# VCO.net
KiCad netlist of a schematic drawn in Altium Designer
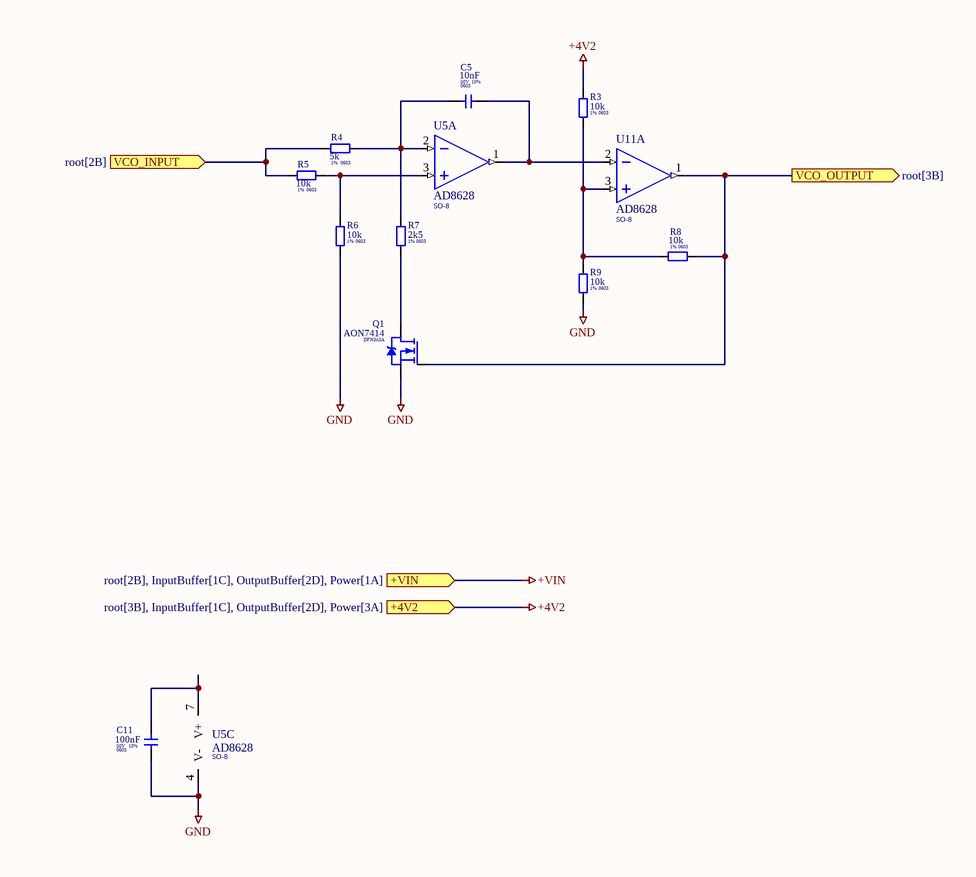
[diagram p0: VCO.SchDoc]

(export (version "E")
  (design (tool "Eeschema 10.0.6"))
  (components
    (comp (ref "C5")
      (value "10nF")
      (footprint "CAPC1608X06M")
      (fields
        (field (name "VOLTAGE") "50V")
        (field (name "TOLERANT") "10%")
        (field (name "PACKAGE") "0603")
        (field (name "Comment") "10nF/50V")
      )
      (libsource (lib "Falcon-SchMain-Lib") (part "C"))
    )
    (comp (ref "C11")
      (value "100nF")
      (footprint "CAPC1608X06M")
      (fields
        (field (name "VOLTAGE") "50V")
        (field (name "TOLERANT") "10%")
        (field (name "PACKAGE") "0603")
        (field (name "Comment") "100nF/50V")
      )
      (libsource (lib "Falcon-SchMain-Lib") (part "C"))
    )
    (comp (ref "Q1")
      (value "AON7414")
      (footprint "SON65P300X90-3L")
      (description "30V, 15A N-Channel MOSFET")
      (fields (field (name "PACKAGE") "DFN3x3A"))
      (libsource (lib "Falcon-SchTransistor-Lib") (part "AON7414"))
    )
    (comp (ref "R3")
      (value "10k")
      (footprint "RESC1608X06L")
      (fields
        (field (name "PACKAGE") "0603")
        (field (name "TOLERANCE") "1%")
        (field (name "Comment") "10k 1%")
      )
      (libsource (lib "") (part "R_1"))
    )
    (comp (ref "R4")
      (value "5k")
      (footprint "RESC1608X06L")
      (fields
        (field (name "PACKAGE") "0603")
        (field (name "TOLERANCE") "1%")
        (field (name "Comment") "5k 1%")
      )
      (libsource (lib "") (part "R_2"))
    )
    (comp (ref "R5")
      (value "10k")
      (footprint "RESC1608X06L")
      (fields
        (field (name "PACKAGE") "0603")
        (field (name "TOLERANCE") "1%")
        (field (name "Comment") "10k 1%")
      )
      (libsource (lib "") (part "R_2"))
    )
    (comp (ref "R6")
      (value "10k")
      (footprint "RESC1608X06L")
      (fields
        (field (name "PACKAGE") "0603")
        (field (name "TOLERANCE") "1%")
        (field (name "Comment") "10k 1%")
      )
      (libsource (lib "") (part "R_1"))
    )
    (comp (ref "R7")
      (value "2k5")
      (footprint "RESC1608X06L")
      (fields
        (field (name "PACKAGE") "0603")
        (field (name "TOLERANCE") "1%")
        (field (name "Comment") "2k5 1%")
      )
      (libsource (lib "") (part "R_1"))
    )
    (comp (ref "R8")
      (value "10k")
      (footprint "RESC1608X06L")
      (fields
        (field (name "PACKAGE") "0603")
        (field (name "TOLERANCE") "1%")
        (field (name "Comment") "10k 1%")
      )
      (libsource (lib "Falcon-SchMain-Lib") (part "R"))
    )
    (comp (ref "R9")
      (value "10k")
      (footprint "RESC1608X06L")
      (fields
        (field (name "PACKAGE") "0603")
        (field (name "TOLERANCE") "1%")
        (field (name "Comment") "10k 1%")
      )
      (libsource (lib "") (part "R_1"))
    )
    (comp (ref "U5")
      (value "AD8628")
      (footprint "SOIC127P600X170-8N")
      (description "Zero-Drift, Single-Supply, Rail-to-Rail Input/Output Operational Amplifier")
      (fields (field (name "PACKAGE") "SO-8"))
      (libsource (lib "") (part "AD8628ARZ_1"))
    )
    (comp (ref "U11")
      (value "AD8628")
      (footprint "SOIC127P600X170-8N")
      (description "Zero-Drift, Single-Supply, Rail-to-Rail Input/Output Operational Amplifier")
      (fields (field (name "PACKAGE") "SO-8"))
      (libsource (lib "") (part "AD8628ARZ_1"))
    )
  )
  (nets
    (net (code "1") (name "+4V2") (class "Default")
      (node (ref "R3") (pin "2") (pinfunction "2_2") (pintype "passive"))
    )
    (net (code "3") (name "/VCO_INPUT") (class "Default")
      (node (ref "R4") (pin "1") (pinfunction "1_1") (pintype "passive"))
      (node (ref "R5") (pin "1") (pinfunction "1_1") (pintype "passive"))
    )
    (net (code "4") (name "/VCO_OUTPUT") (class "Default")
      (node (ref "Q1") (pin "2") (pinfunction "G_2") (pintype "passive"))
      (node (ref "R8") (pin "1") (pinfunction "1_1") (pintype "passive"))
      (node (ref "U11") (pin "1") (pinfunction "OUT_1") (pintype "output"))
    )
    (net (code "5") (name "GND") (class "Default")
      (node (ref "C11") (pin "1") (pinfunction "1_1") (pintype "passive"))
      (node (ref "Q1") (pin "1") (pinfunction "S_1") (pintype "passive"))
      (node (ref "R6") (pin "1") (pinfunction "1_1") (pintype "passive"))
      (node (ref "R9") (pin "1") (pinfunction "1_1") (pintype "passive"))
      (node (ref "U5") (pin "4") (pinfunction "V-_4") (pintype "power_in"))
    )
    (net (code "6") (name "Net-(Q1-D)") (class "Default")
      (node (ref "Q1") (pin "3") (pinfunction "D_3") (pintype "passive"))
      (node (ref "R7") (pin "1") (pinfunction "1_1") (pintype "passive"))
    )
    (net (code "7") (name "Net-(U5A-IN+)") (class "Default")
      (node (ref "R5") (pin "2") (pinfunction "2_2") (pintype "passive"))
      (node (ref "R6") (pin "2") (pinfunction "2_2") (pintype "passive"))
      (node (ref "U5") (pin "3") (pinfunction "IN+_3") (pintype "input"))
    )
    (net (code "8") (name "Net-(U5A-IN-)") (class "Default")
      (node (ref "C5") (pin "1") (pinfunction "1_1") (pintype "passive"))
      (node (ref "R4") (pin "2") (pinfunction "2_2") (pintype "passive"))
      (node (ref "R7") (pin "2") (pinfunction "2_2") (pintype "passive"))
      (node (ref "U5") (pin "2") (pinfunction "IN-_2") (pintype "input"))
    )
    (net (code "9") (name "Net-(U5C-V+)") (class "Default")
      (node (ref "C11") (pin "2") (pinfunction "2_2") (pintype "passive"))
      (node (ref "U5") (pin "7") (pinfunction "V+_7") (pintype "power_in"))
    )
    (net (code "10") (name "Net-(U11A-IN+)") (class "Default")
      (node (ref "R3") (pin "1") (pinfunction "1_1") (pintype "passive"))
      (node (ref "R8") (pin "2") (pinfunction "2_2") (pintype "passive"))
      (node (ref "R9") (pin "2") (pinfunction "2_2") (pintype "passive"))
      (node (ref "U11") (pin "3") (pinfunction "IN+_3") (pintype "input"))
    )
    (net (code "11") (name "Net-(U11A-IN-)") (class "Default")
      (node (ref "C5") (pin "2") (pinfunction "2_2") (pintype "passive"))
      (node (ref "U11") (pin "2") (pinfunction "IN-_2") (pintype "input"))
      (node (ref "U5") (pin "1") (pinfunction "OUT_1") (pintype "output"))
    )
  )
)
